# Sheet1.net
KiCad netlist of a schematic drawn in Altium Designer
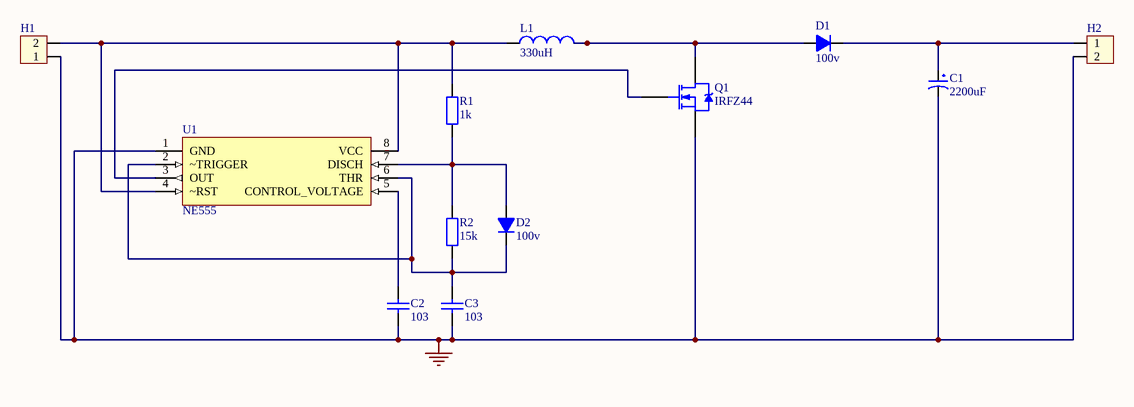
[diagram p0: Sheet1.SchDoc]

(export (version "E")
  (design (tool "Eeschema 10.0.6"))
  (components
    (comp (ref "C1")
      (value "2200uF")
      (footprint "tu hoa 13mm")
      (description "Cắm")
      (libsource (lib "Tu dien") (part "Tu Hoa 2200uF 25V 13x20"))
    )
    (comp (ref "C2")
      (value "103")
      (footprint "tu gom")
      (description "Cắm")
      (libsource (lib "Tu dien") (part "Tu gom 103 50V"))
    )
    (comp (ref "C3")
      (value "103")
      (footprint "tu gom")
      (description "Cắm")
      (libsource (lib "Tu dien") (part "Tu gom 103 50V"))
    )
    (comp (ref "D1")
      (value "100v")
      (footprint "DIODE 1A")
      (description "Cắm")
      (libsource (lib "Diode") (part "Diode 1N4007"))
    )
    (comp (ref "D2")
      (value "100v")
      (footprint "DIODE 0.5A")
      (description "Cắm")
      (libsource (lib "Diode") (part "Diode 1N4148"))
    )
    (comp (ref "H1")
      (value "Header 2P 2.54 Duc Cong")
      (footprint "Header 2P DC 2.54")
      (description "Cắm")
      (libsource (lib "") (part "Header 2P 2.54 Duc Cong_1"))
    )
    (comp (ref "H2")
      (value "Header 2P 2.54 Duc Cong")
      (footprint "Header 2P DC 2.54")
      (description "Cắm")
      (libsource (lib "Header") (part "Header 2P 2.54 Duc Cong"))
    )
    (comp (ref "L1")
      (value "330uH")
      (footprint "IND_30.1MM_TH")
      (description "330uH-10A-CHINESE INDUCTOR")
      (fields (field (name "MANUFACTURER PART NUMBER") "NA"))
      (libsource (lib "Cuon Cam") (part "IND_330uH-10A-TH"))
    )
    (comp (ref "Q1")
      (value "IRFZ44")
      (footprint "TO220")
      (description "N-Channel Power MOSFET")
      (libsource (lib "TranFet") (part "IRFZ44 DIP"))
    )
    (comp (ref "R1")
      (value "1k")
      (footprint "tro vach 1w")
      (description "Cắm")
      (libsource (lib "Dien Tro") (part "Tro Vach 1W 5% 1k"))
    )
    (comp (ref "R2")
      (value "15k")
      (footprint "tro vach 1w")
      (description "Cắm")
      (libsource (lib "Dien Tro") (part "Tro Vach 1W 5% 15k"))
    )
    (comp (ref "U1")
      (value "NE555")
      (footprint "PDIP-8_100_393_66X66_TH")
      (description "555 Type, Timer/Oscillator (Single) IC 3MHz 8-PDIP")
      (fields
        (field (name "MANUFACTURER") "Texas Instruments")
        (field (name "MANUFACTURER PART NUMBER") "LMC555CN/NOPB")
      )
      (libsource (lib "IC") (part "IC_LMC555CN/NOPB"))
    )
  )
  (nets
    (net (code "1") (name "GND") (class "Default")
      (node (ref "C1") (pin "2") (pinfunction "2_2") (pintype "passive"))
      (node (ref "C2") (pin "2") (pinfunction "2_2") (pintype "passive"))
      (node (ref "C3") (pin "2") (pinfunction "2_2") (pintype "passive"))
      (node (ref "H1") (pin "1") (pinfunction "1_1") (pintype "passive"))
      (node (ref "H2") (pin "2") (pinfunction "2_2") (pintype "passive"))
      (node (ref "Q1") (pin "3") (pinfunction "S_3") (pintype "passive"))
      (node (ref "U1") (pin "1") (pinfunction "GND_1") (pintype "passive"))
    )
    (net (code "2") (name "Net-(D1-A)") (class "Default")
      (node (ref "D1") (pin "1") (pinfunction "A_1") (pintype "passive"))
      (node (ref "L1") (pin "2") (pinfunction "2_2") (pintype "passive"))
      (node (ref "Q1") (pin "2") (pinfunction "D_2") (pintype "passive"))
    )
    (net (code "3") (name "Net-(D1-K)") (class "Default")
      (node (ref "C1") (pin "1") (pinfunction "1_1") (pintype "passive"))
      (node (ref "D1") (pin "2") (pinfunction "K_2") (pintype "passive"))
      (node (ref "H2") (pin "1") (pinfunction "1_1") (pintype "passive"))
    )
    (net (code "4") (name "Net-(D2-A)") (class "Default")
      (node (ref "D2") (pin "1") (pinfunction "A_1") (pintype "passive"))
      (node (ref "R1") (pin "1") (pinfunction "1_1") (pintype "passive"))
      (node (ref "R2") (pin "1") (pinfunction "1_1") (pintype "passive"))
      (node (ref "U1") (pin "7") (pinfunction "DISCH_7") (pintype "input"))
    )
    (net (code "5") (name "Net-(D2-K)") (class "Default")
      (node (ref "C3") (pin "1") (pinfunction "1_1") (pintype "passive"))
      (node (ref "D2") (pin "2") (pinfunction "K_2") (pintype "passive"))
      (node (ref "R2") (pin "2") (pinfunction "2_2") (pintype "passive"))
      (node (ref "U1") (pin "2") (pinfunction "~TRIGGER_2") (pintype "input"))
      (node (ref "U1") (pin "6") (pinfunction "THR_6") (pintype "input"))
    )
    (net (code "6") (name "Net-(Q1-G)") (class "Default")
      (node (ref "Q1") (pin "1") (pinfunction "G_1") (pintype "passive"))
      (node (ref "U1") (pin "3") (pinfunction "OUT_3") (pintype "output"))
    )
    (net (code "7") (name "Net-(U1-CONTROL_VOLTAGE)") (class "Default")
      (node (ref "C2") (pin "1") (pinfunction "1_1") (pintype "passive"))
      (node (ref "U1") (pin "5") (pinfunction "CONTROL_VOLTAGE_5") (pintype "input"))
    )
    (net (code "8") (name "Net-(U1-VCC)") (class "Default")
      (node (ref "H1") (pin "2") (pinfunction "2_2") (pintype "passive"))
      (node (ref "L1") (pin "1") (pinfunction "1_1") (pintype "passive"))
      (node (ref "R1") (pin "2") (pinfunction "2_2") (pintype "passive"))
      (node (ref "U1") (pin "4") (pinfunction "~RST_4") (pintype "input"))
      (node (ref "U1") (pin "8") (pinfunction "VCC_8") (pintype "power_in"))
    )
  )
)
